# Power_Monitor.net
KiCad netlist of a schematic drawn in Altium Designer
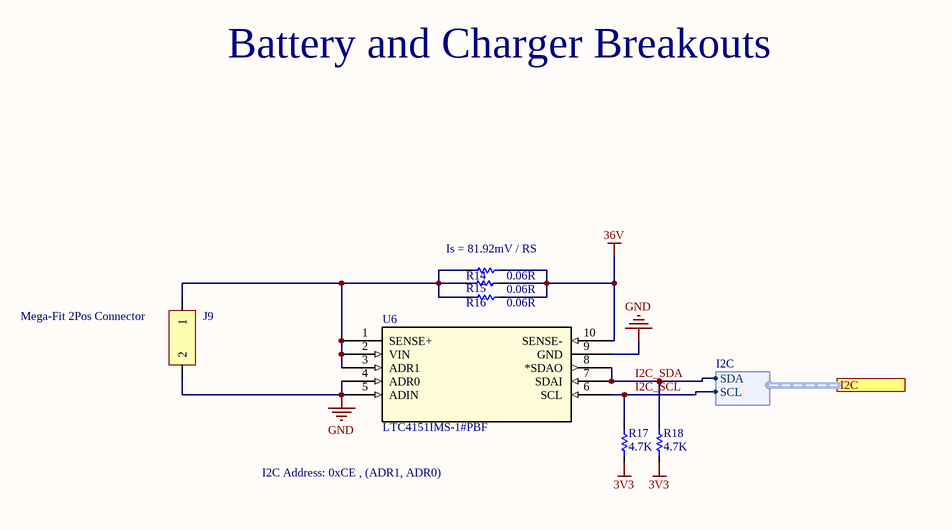
[diagram p0: Power_Monitor.SchDoc]

(export (version "E")
  (design (tool "Eeschema 10.0.6"))
  (components
    (comp (ref "J9")
      (value "Mega-Fit 2Pos Connector")
      (footprint "MegaFit-2Pos")
      (description "Molex MegaFit 2-Pos Connector")
      (libsource (lib "LaunchyRIOComponents") (part "Mega-Fit 2Pos"))
    )
    (comp (ref "R14")
      (value "0.06R")
      (footprint "RES_0603")
      (fields (field (name "Comment") "Res"))
      (libsource (lib "Generic_Library") (part "Res"))
    )
    (comp (ref "R15")
      (value "0.06R")
      (footprint "RES_0603")
      (fields (field (name "Comment") "Res"))
      (libsource (lib "Generic_Library") (part "Res"))
    )
    (comp (ref "R16")
      (value "0.06R")
      (footprint "RES_0603")
      (fields (field (name "Comment") "Res"))
      (libsource (lib "Generic_Library") (part "Res"))
    )
    (comp (ref "R17")
      (value "4.7K")
      (footprint "RES_0603")
      (fields (field (name "Comment") "Res"))
      (libsource (lib "Generic_Library") (part "Res"))
    )
    (comp (ref "R18")
      (value "4.7K")
      (footprint "RES_0603")
      (fields (field (name "Comment") "Res"))
      (libsource (lib "Generic_Library") (part "Res"))
    )
    (comp (ref "U6")
      (value "LTC4151IMS-1#PBF")
      (footprint "MSOP-10_MS")
      (description "Imported")
      (fields
        (field (name "MANUFACTURER_PART_NUMBER") "ltc4151ims-1#pbf")
        (field (name "COPYRIGHT") "Copyright (C) 2016 Accelerated Designs. All rights reserved")
      )
      (libsource (lib "LaunchyRIOComponents") (part "LTC4151IMS-1#PBF"))
    )
  )
  (nets
    (net (code "2") (name "/I2C_SCL") (class "Default")
      (node (ref "R17") (pin "2") (pinfunction "2_2") (pintype "passive"))
      (node (ref "U6") (pin "6") (pinfunction "SCL_6") (pintype "input"))
    )
    (net (code "3") (name "/I2C_SDA") (class "Default")
      (node (ref "R18") (pin "2") (pinfunction "2_2") (pintype "passive"))
      (node (ref "U6") (pin "7") (pinfunction "SDAI_7") (pintype "input"))
      (node (ref "U6") (pin "8") (pinfunction "*SDAO_8") (pintype "output"))
    )
    (net (code "5") (name "3V3") (class "Default")
      (node (ref "R17") (pin "1") (pinfunction "1_1") (pintype "passive"))
      (node (ref "R18") (pin "1") (pinfunction "1_1") (pintype "passive"))
    )
    (net (code "6") (name "36V") (class "Default")
      (node (ref "R14") (pin "2") (pinfunction "2_2") (pintype "passive"))
      (node (ref "R15") (pin "2") (pinfunction "2_2") (pintype "passive"))
      (node (ref "R16") (pin "2") (pinfunction "2_2") (pintype "passive"))
      (node (ref "U6") (pin "10") (pinfunction "SENSE-_10") (pintype "input"))
    )
    (net (code "7") (name "GND") (class "Default")
      (node (ref "J9") (pin "2") (pinfunction "2_2") (pintype "passive"))
      (node (ref "U6") (pin "4") (pinfunction "ADR0_4") (pintype "input"))
      (node (ref "U6") (pin "5") (pinfunction "ADIN_5") (pintype "input"))
      (node (ref "U6") (pin "9") (pinfunction "GND_9") (pintype "power_in"))
    )
    (net (code "8") (name "Net-(U6-ADR1)") (class "Default")
      (node (ref "J9") (pin "1") (pinfunction "1_1") (pintype "passive"))
      (node (ref "R14") (pin "1") (pinfunction "1_1") (pintype "passive"))
      (node (ref "R15") (pin "1") (pinfunction "1_1") (pintype "passive"))
      (node (ref "R16") (pin "1") (pinfunction "1_1") (pintype "passive"))
      (node (ref "U6") (pin "1") (pinfunction "SENSE+_1") (pintype "passive"))
      (node (ref "U6") (pin "2") (pinfunction "VIN_2") (pintype "input"))
      (node (ref "U6") (pin "3") (pinfunction "ADR1_3") (pintype "input"))
    )
  )
)
